# MCU.net
KiCad netlist of a schematic drawn in Altium Designer
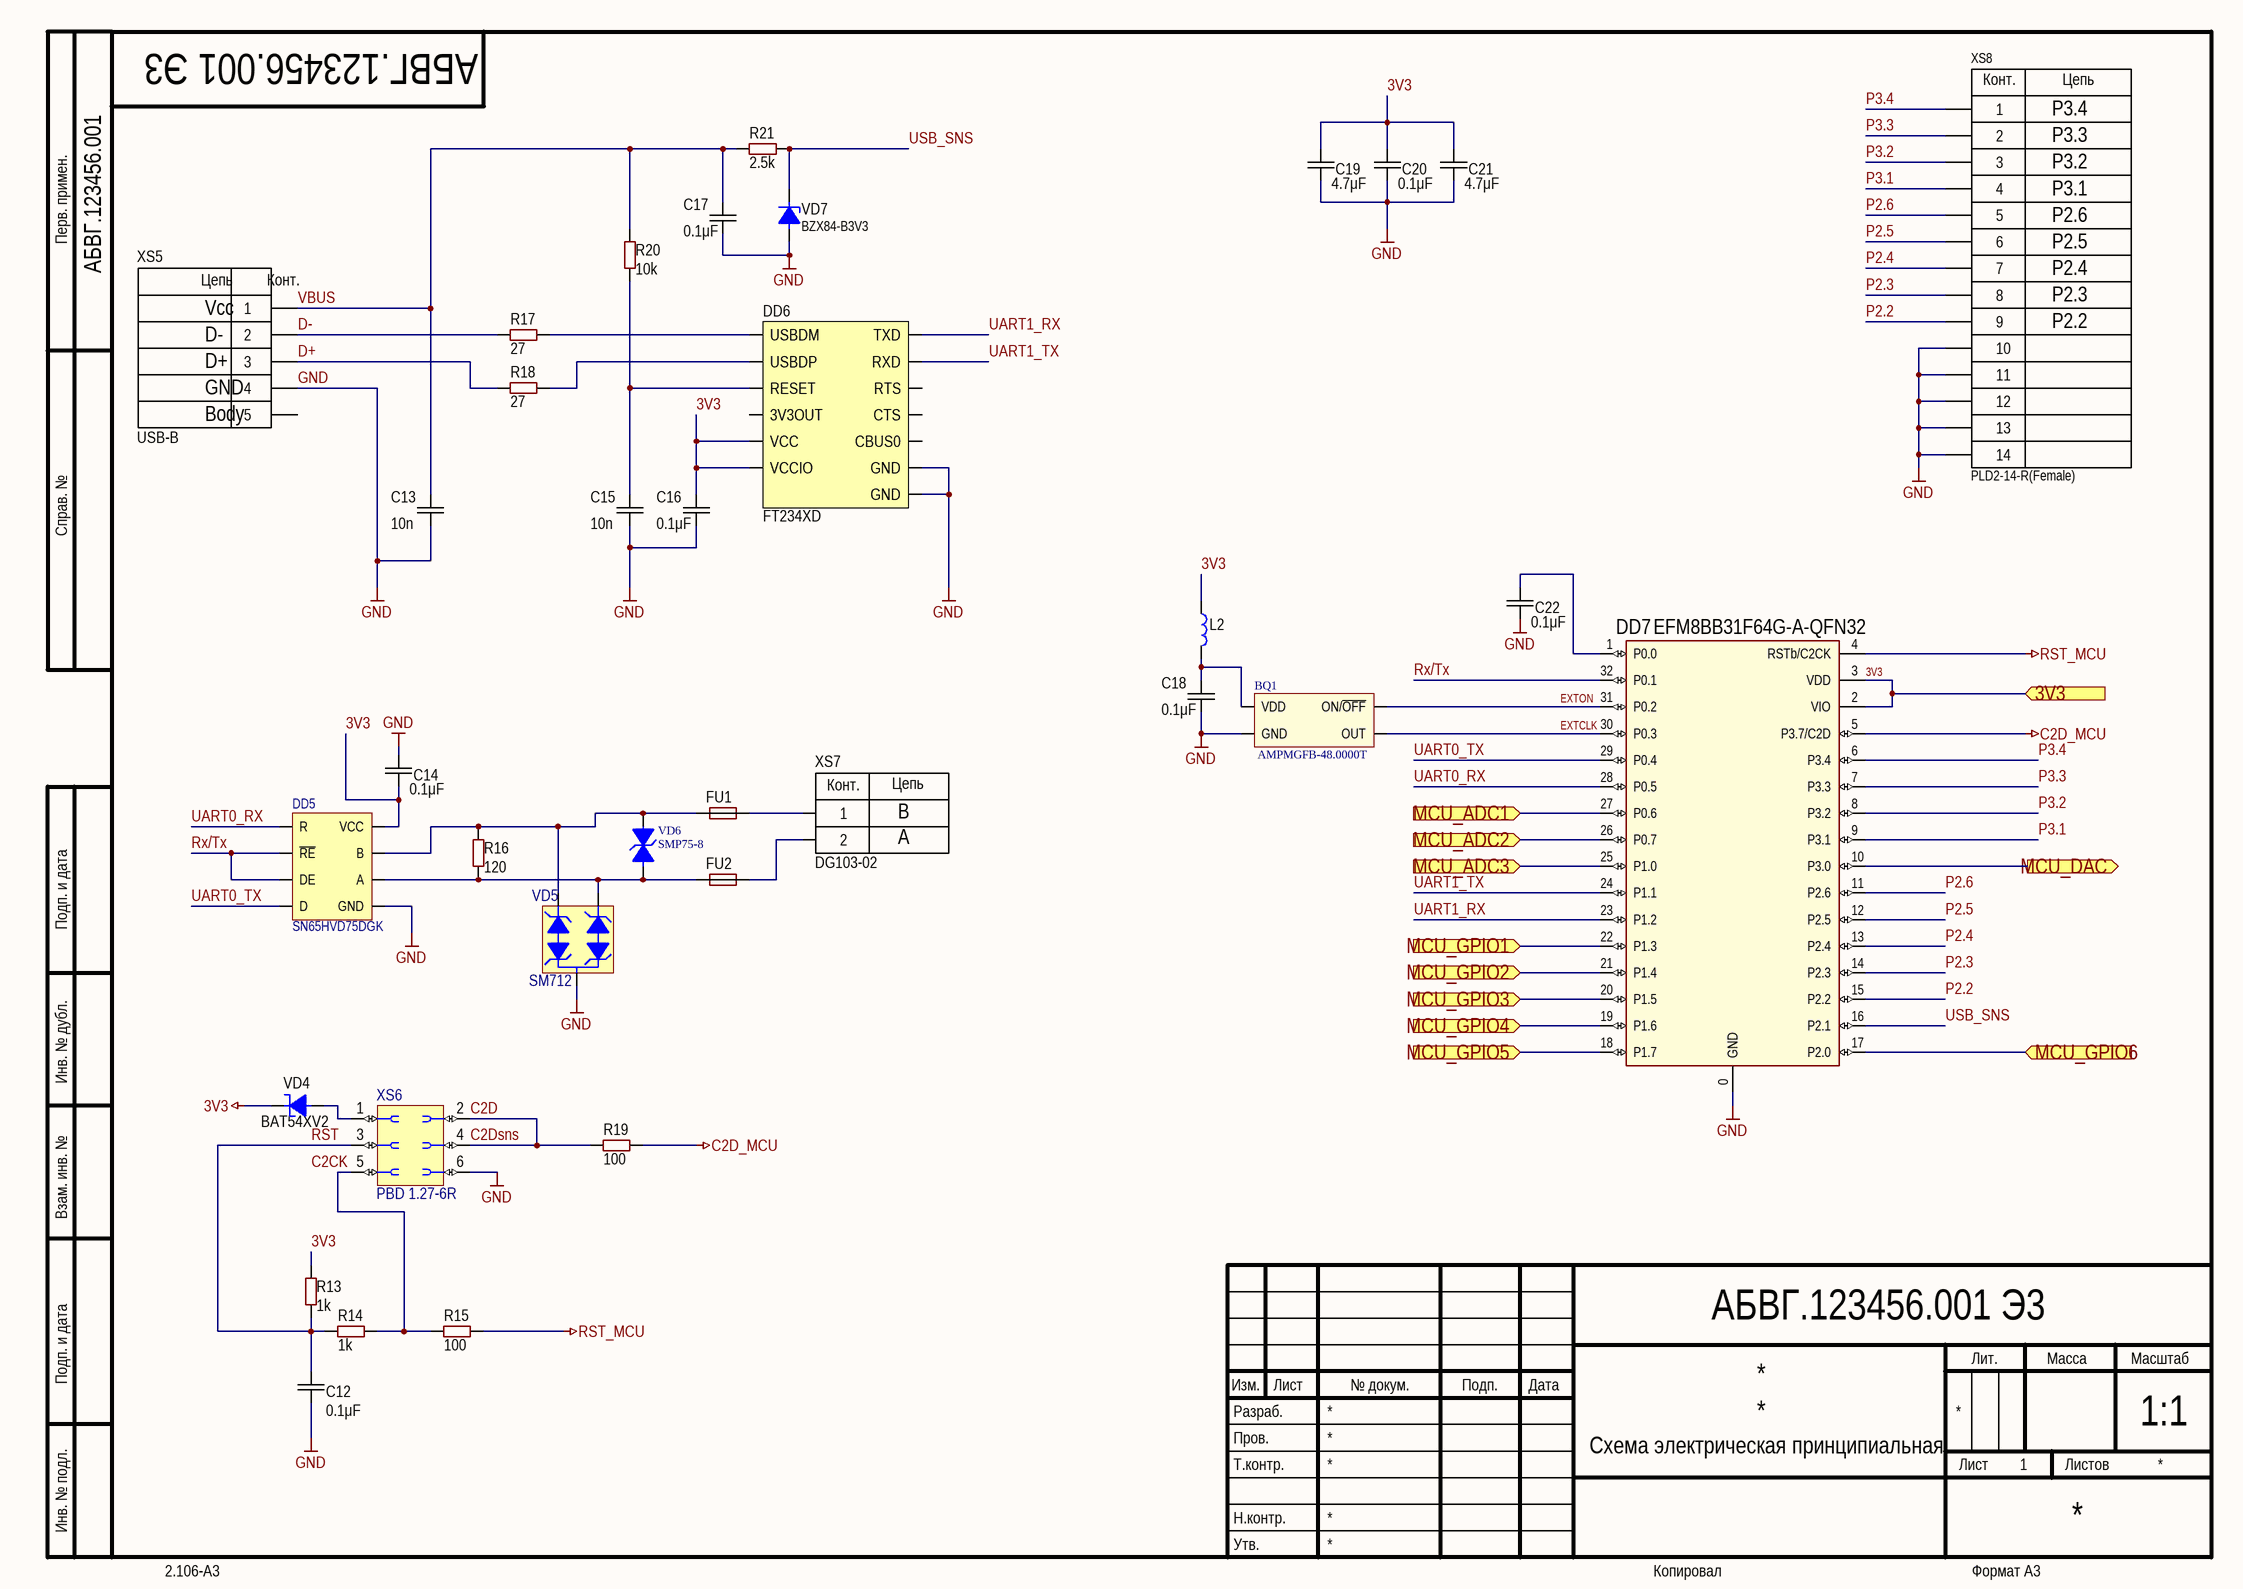
[diagram p0: MCU.SchDoc]

(export (version "E")
  (design (tool "Eeschema 10.0.6"))
  (components
    (comp (ref "BQ1")
      (value "AMPMGFB-48.0000T")
      (footprint "AMPMGFB(1.6x1.2)")
      (libsource (lib "oscilator") (part "AMPMGFB-48.0000T"))
    )
    (comp (ref "C12")
      (value "0.1μF")
      (footprint "CAP: 0603")
      (fields
        (field (name "MANUFACTURER") "Yageo")
        (field (name "PARTNUMBER") "CC0603KRX7R7BB104")
        (field (name "VALUEMANUFACTURERPARTNUMBER") "Ceramic capacitor, 0.1μF, X7R, ±10%, 16V, 0603, -55...+125°C")
      )
      (libsource (lib "capacitor") (part "Ceramic_0603"))
    )
    (comp (ref "C13")
      (value "10n")
      (footprint "CAP: 0603")
      (fields
        (field (name "MANUFACTURER") "Yageo")
        (field (name "PARTNUMBER") "CC0603KRX7R7BB104")
        (field (name "VALUEMANUFACTURERPARTNUMBER") "Ceramic capacitor, 10n, X7R, ±10%, 16V, 0603, -55...+125°C")
      )
      (libsource (lib "capacitor") (part "Ceramic_0603"))
    )
    (comp (ref "C14")
      (value "0.1μF")
      (footprint "CAP: 0603")
      (fields
        (field (name "MANUFACTURER") "Yageo")
        (field (name "PARTNUMBER") "CC0603KRX7R7BB104")
        (field (name "VALUEMANUFACTURERPARTNUMBER") "Ceramic capacitor, 0.1μF, X7R, ±10%, 16V, 0603, -55...+125°C")
      )
      (libsource (lib "capacitor") (part "Ceramic_0603"))
    )
    (comp (ref "C15")
      (value "10n")
      (footprint "CAP: 0603")
      (fields
        (field (name "MANUFACTURER") "Yageo")
        (field (name "PARTNUMBER") "CC0603KRX7R7BB104")
        (field (name "VALUEMANUFACTURERPARTNUMBER") "Ceramic capacitor, 10n, X7R, ±10%, 16V, 0603, -55...+125°C")
      )
      (libsource (lib "capacitor") (part "Ceramic_0603"))
    )
    (comp (ref "C16")
      (value "0.1μF")
      (footprint "CAP: 0603")
      (fields
        (field (name "MANUFACTURER") "Yageo")
        (field (name "PARTNUMBER") "CC0603KRX7R7BB104")
        (field (name "VALUEMANUFACTURERPARTNUMBER") "Ceramic capacitor, 0.1μF, X7R, ±10%, 16V, 0603, -55...+125°C")
      )
      (libsource (lib "capacitor") (part "Ceramic_0603"))
    )
    (comp (ref "C17")
      (value "0.1μF")
      (footprint "CAP: 0603")
      (fields
        (field (name "MANUFACTURER") "Yageo")
        (field (name "PARTNUMBER") "CC0603KRX7R7BB104")
        (field (name "VALUEMANUFACTURERPARTNUMBER") "Ceramic capacitor, 0.1μF, X7R, ±10%, 16V, 0603, -55...+125°C")
      )
      (libsource (lib "capacitor") (part "Ceramic_0603"))
    )
    (comp (ref "C18")
      (value "0.1μF")
      (footprint "CAP: 0603")
      (fields
        (field (name "MANUFACTURER") "Yageo")
        (field (name "PARTNUMBER") "CC0603KRX7R7BB104")
        (field (name "VALUEMANUFACTURERPARTNUMBER") "Ceramic capacitor, 0.1μF, X7R, ±10%, 16V, 0603, -55...+125°C")
      )
      (libsource (lib "capacitor") (part "Ceramic_0603"))
    )
    (comp (ref "C19")
      (value "4.7μF")
      (footprint "CAP: 0603")
      (fields
        (field (name "MANUFACTURER") "Yageo")
        (field (name "PARTNUMBER") "CC0603KRX7R7BB104")
        (field (name "VALUEMANUFACTURERPARTNUMBER") "Ceramic capacitor, 4.7μF, X7R, ±10%, 16V, 0603, -55...+125°C")
      )
      (libsource (lib "capacitor") (part "Ceramic_0603"))
    )
    (comp (ref "C20")
      (value "0.1μF")
      (footprint "CAP: 0603")
      (fields
        (field (name "MANUFACTURER") "Yageo")
        (field (name "PARTNUMBER") "CC0603KRX7R7BB104")
        (field (name "VALUEMANUFACTURERPARTNUMBER") "Ceramic capacitor, 0.1μF, X7R, ±10%, 16V, 0603, -55...+125°C")
      )
      (libsource (lib "capacitor") (part "Ceramic_0603"))
    )
    (comp (ref "C21")
      (value "4.7μF")
      (footprint "CAP: 0603")
      (fields
        (field (name "MANUFACTURER") "Yageo")
        (field (name "PARTNUMBER") "CC0603KRX7R7BB104")
        (field (name "VALUEMANUFACTURERPARTNUMBER") "Ceramic capacitor, 4.7μF, X7R, ±10%, 16V, 0603, -55...+125°C")
      )
      (libsource (lib "capacitor") (part "Ceramic_0603"))
    )
    (comp (ref "C22")
      (value "0.1μF")
      (footprint "CAP: 0603")
      (fields
        (field (name "MANUFACTURER") "Yageo")
        (field (name "PARTNUMBER") "CC0603KRX7R7BB104")
        (field (name "VALUEMANUFACTURERPARTNUMBER") "Ceramic capacitor, 0.1μF, X7R, ±10%, 16V, 0603, -55...+125°C")
      )
      (libsource (lib "capacitor") (part "Ceramic_0603"))
    )
    (comp (ref "DD5")
      (value "SN65HVD75DGK")
      (footprint "VSSOP-8")
      (description "RS-485/422")
      (libsource (lib "ic-interface") (part "SN65HVD72DGK"))
    )
    (comp (ref "DD6")
      (value "FT234XD")
      (footprint "12-DFN")
      (description "USB-UART")
      (libsource (lib "ic-interface") (part "FT234XD"))
    )
    (comp (ref "DD7")
      (value "EFM8BB31F64G-A-QFN32")
      (footprint "32-QFN(4x4)")
      (description "8051 MCU Core")
      (libsource (lib "ic-mcu") (part "EFM8BB31F64G-A-QFN32"))
    )
    (comp (ref "FU1")
      (value "~")
      (footprint "FUSE: 0603")
      (fields
        (field (name "MANUFACTURER") "Littelfuse")
        (field (name "VALUEMANUFACTURERPARTNUMBER") "Electromechanics relay, 250VAC, , 5x20mm, ")
        (field (name "PARTNUMBER") "01110501Z")
      )
      (libsource (lib "electromechanics") (part "Fuse"))
    )
    (comp (ref "FU2")
      (value "~")
      (footprint "FUSE: 0603")
      (fields
        (field (name "MANUFACTURER") "Littelfuse")
        (field (name "VALUEMANUFACTURERPARTNUMBER") "Electromechanics relay, 250VAC, , 5x20mm, ")
        (field (name "PARTNUMBER") "01110501Z")
      )
      (libsource (lib "electromechanics") (part "Fuse"))
    )
    (comp (ref "L2")
      (value "BLM18AG102SN1D")
      (footprint "IND: 0603")
      (description "100MHz 1K")
      (libsource (lib "inductor") (part "BLM18AG102SN1D"))
    )
    (comp (ref "R13")
      (value "1k")
      (footprint "RES: 0603")
      (fields
        (field (name "MANUFACTURER") "Yageo")
        (field (name "PARTNUMBER") "RC0603JR-07100RL")
        (field (name "VALUEMANUFACTURERPARTNUMBER") "Resistor film, 1k, ±5%, 0603, 0.1W, -55...+125°C")
      )
      (libsource (lib "resistor") (part "Resistor_0603"))
    )
    (comp (ref "R14")
      (value "1k")
      (footprint "RES: 0603")
      (fields
        (field (name "MANUFACTURER") "Yageo")
        (field (name "PARTNUMBER") "RC0603JR-07100RL")
        (field (name "VALUEMANUFACTURERPARTNUMBER") "Resistor film, 1k, ±5%, 0603, 0.1W, -55...+125°C")
      )
      (libsource (lib "") (part "Resistor_0603_1"))
    )
    (comp (ref "R15")
      (value "100")
      (footprint "RES: 0603")
      (fields
        (field (name "MANUFACTURER") "Yageo")
        (field (name "PARTNUMBER") "RC0603JR-07100RL")
        (field (name "VALUEMANUFACTURERPARTNUMBER") "Resistor film, 100, ±5%, 0603, 0.1W, -55...+125°C")
      )
      (libsource (lib "") (part "Resistor_0603_1"))
    )
    (comp (ref "R16")
      (value "120")
      (footprint "RES: 0603")
      (fields
        (field (name "MANUFACTURER") "Yageo")
        (field (name "PARTNUMBER") "RC0603JR-07100RL")
        (field (name "VALUEMANUFACTURERPARTNUMBER") "Resistor film, 120, ±5%, 0603, 0.1W, -55...+125°C")
      )
      (libsource (lib "") (part "Resistor_0603_1"))
    )
    (comp (ref "R17")
      (value "27")
      (footprint "RES: 0603")
      (fields
        (field (name "MANUFACTURER") "Yageo")
        (field (name "PARTNUMBER") "RC0603JR-07100RL")
        (field (name "VALUEMANUFACTURERPARTNUMBER") "Resistor film, 27, ±5%, 0603, 0.1W, -55...+125°C")
      )
      (libsource (lib "resistor") (part "Resistor_0603"))
    )
    (comp (ref "R18")
      (value "27")
      (footprint "RES: 0603")
      (fields
        (field (name "MANUFACTURER") "Yageo")
        (field (name "PARTNUMBER") "RC0603JR-07100RL")
        (field (name "VALUEMANUFACTURERPARTNUMBER") "Resistor film, 27, ±5%, 0603, 0.1W, -55...+125°C")
      )
      (libsource (lib "resistor") (part "Resistor_0603"))
    )
    (comp (ref "R19")
      (value "100")
      (footprint "RES: 0603")
      (fields
        (field (name "MANUFACTURER") "Yageo")
        (field (name "PARTNUMBER") "RC0603JR-07100RL")
        (field (name "VALUEMANUFACTURERPARTNUMBER") "Resistor film, 100, ±5%, 0603, 0.1W, -55...+125°C")
      )
      (libsource (lib "resistor") (part "Resistor_0603"))
    )
    (comp (ref "R20")
      (value "10k")
      (footprint "RES: 0603")
      (fields
        (field (name "MANUFACTURER") "Yageo")
        (field (name "PARTNUMBER") "RC0603JR-07100RL")
        (field (name "VALUEMANUFACTURERPARTNUMBER") "Resistor film, 10k, ±5%, 0603, 0.1W, -55...+125°C")
      )
      (libsource (lib "") (part "Resistor_0603_1"))
    )
    (comp (ref "R21")
      (value "2.5k")
      (footprint "RES: 0603")
      (fields
        (field (name "MANUFACTURER") "Yageo")
        (field (name "PARTNUMBER") "RC0603JR-07100RL")
        (field (name "VALUEMANUFACTURERPARTNUMBER") "Resistor film, 2.5k, ±5%, 0603, 0.1W, -55...+125°C")
      )
      (libsource (lib "resistor") (part "Resistor_0603"))
    )
    (comp (ref "VD4")
      (value "~")
      (footprint "DIODE: SOD523")
      (fields
        (field (name "MANUFACTURER") "Diodes Incorporated")
        (field (name "VALUEMANUFACTURERPARTNUMBER") "Schottky diode, 80V, 500mA, 1V, 15pF, SOD-123, -55...+150°C")
        (field (name "VOLTAGE") "80V")
        (field (name "PARTNUMBER") "BAT54XV2")
      )
      (libsource (lib "diode") (part "Schottky_single"))
    )
    (comp (ref "VD5")
      (value "SM712")
      (footprint "SOT23")
      (description "EIA RS-485 ±7V ±12V")
      (libsource (lib "diode") (part "SM712"))
    )
    (comp (ref "VD6")
      (value "SMP75-8")
      (footprint "DIODE: SMB")
      (libsource (lib "diode") (part "SMBJ10CA-TR"))
    )
    (comp (ref "VD7") (value "BZX84-B3V3") (footprint "SOT23") (libsource (lib "diode") (part "BZX84-B3V3")))
    (comp (ref "XS5")
      (value "USB-B")
      (footprint "CON: USB-B(Female vertical)")
      (libsource (lib "connector") (part "USB-B"))
    )
    (comp (ref "XS6")
      (value "PBD 1.27-6R")
      (footprint "CON: PLLD-6R(1.27)")
      (libsource (lib "connector") (part "PBD 1.27-6R"))
    )
    (comp (ref "XS7")
      (value "DG103-02")
      (footprint "DG103-02")
      (libsource (lib "connector") (part "DG103-02"))
    )
    (comp (ref "XS8")
      (value "PLD2-14-R(Female)")
      (footprint "CON: PLD2-14-R(Female)")
      (libsource (lib "connector") (part "PLD2-14(Female)"))
    )
  )
  (nets
    (net (code "2") (name "/C2D") (class "Default")
      (node (ref "R19") (pin "2") (pinfunction "2_2") (pintype "passive"))
      (node (ref "XS6") (pin "2") (pinfunction "2_2") (pintype "bidirectional"))
      (node (ref "XS6") (pin "4") (pinfunction "4_4") (pintype "bidirectional"))
    )
    (net (code "3") (name "/D+") (class "Default")
      (node (ref "R18") (pin "2") (pinfunction "2_2") (pintype "passive"))
      (node (ref "XS5") (pin "3") (pinfunction "3_3") (pintype "passive"))
    )
    (net (code "4") (name "/D-") (class "Default")
      (node (ref "R17") (pin "2") (pinfunction "2_2") (pintype "passive"))
      (node (ref "XS5") (pin "2") (pinfunction "2_2") (pintype "passive"))
    )
    (net (code "5") (name "/EXTCLK") (class "Default")
      (node (ref "BQ1") (pin "3") (pinfunction "OUT_3") (pintype "passive"))
      (node (ref "DD7") (pin "30") (pinfunction "P0.3_30") (pintype "bidirectional"))
    )
    (net (code "6") (name "/EXTON") (class "Default")
      (node (ref "BQ1") (pin "1") (pinfunction "ON/~{OFF}_1") (pintype "passive"))
      (node (ref "DD7") (pin "31") (pinfunction "P0.2_31") (pintype "bidirectional"))
    )
    (net (code "7") (name "/MCU_ADC1") (class "Default")
      (node (ref "DD7") (pin "27") (pinfunction "P0.6_27") (pintype "bidirectional"))
    )
    (net (code "8") (name "/MCU_ADC2") (class "Default")
      (node (ref "DD7") (pin "26") (pinfunction "P0.7_26") (pintype "bidirectional"))
    )
    (net (code "9") (name "/MCU_ADC3") (class "Default")
      (node (ref "DD7") (pin "25") (pinfunction "P1.0_25") (pintype "bidirectional"))
    )
    (net (code "10") (name "/MCU_DAC") (class "Default")
      (node (ref "DD7") (pin "10") (pinfunction "P3.0_10") (pintype "bidirectional"))
    )
    (net (code "11") (name "/MCU_GPIO1") (class "Default")
      (node (ref "DD7") (pin "22") (pinfunction "P1.3_22") (pintype "bidirectional"))
    )
    (net (code "12") (name "/MCU_GPIO2") (class "Default")
      (node (ref "DD7") (pin "21") (pinfunction "P1.4_21") (pintype "bidirectional"))
    )
    (net (code "13") (name "/MCU_GPIO3") (class "Default")
      (node (ref "DD7") (pin "20") (pinfunction "P1.5_20") (pintype "bidirectional"))
    )
    (net (code "14") (name "/MCU_GPIO4") (class "Default")
      (node (ref "DD7") (pin "19") (pinfunction "P1.6_19") (pintype "bidirectional"))
    )
    (net (code "15") (name "/MCU_GPIO5") (class "Default")
      (node (ref "DD7") (pin "18") (pinfunction "P1.7_18") (pintype "bidirectional"))
    )
    (net (code "16") (name "/MCU_GPIO6") (class "Default")
      (node (ref "DD7") (pin "17") (pinfunction "P2.0_17") (pintype "bidirectional"))
    )
    (net (code "17") (name "/P2.2") (class "Default")
      (node (ref "DD7") (pin "15") (pinfunction "P2.2_15") (pintype "bidirectional"))
      (node (ref "XS8") (pin "9") (pinfunction "9_9") (pintype "power_in"))
    )
    (net (code "18") (name "/P2.3") (class "Default")
      (node (ref "DD7") (pin "14") (pinfunction "P2.3_14") (pintype "bidirectional"))
      (node (ref "XS8") (pin "8") (pinfunction "8_8") (pintype "power_in"))
    )
    (net (code "19") (name "/P2.4") (class "Default")
      (node (ref "DD7") (pin "13") (pinfunction "P2.4_13") (pintype "bidirectional"))
      (node (ref "XS8") (pin "7") (pinfunction "7_7") (pintype "power_in"))
    )
    (net (code "20") (name "/P2.5") (class "Default")
      (node (ref "DD7") (pin "12") (pinfunction "P2.5_12") (pintype "bidirectional"))
      (node (ref "XS8") (pin "6") (pinfunction "6_6") (pintype "power_in"))
    )
    (net (code "21") (name "/P2.6") (class "Default")
      (node (ref "DD7") (pin "11") (pinfunction "P2.6_11") (pintype "bidirectional"))
      (node (ref "XS8") (pin "5") (pinfunction "5_5") (pintype "power_in"))
    )
    (net (code "22") (name "/P3.1") (class "Default")
      (node (ref "DD7") (pin "9") (pinfunction "P3.1_9") (pintype "bidirectional"))
      (node (ref "XS8") (pin "4") (pinfunction "4_4") (pintype "power_in"))
    )
    (net (code "23") (name "/P3.2") (class "Default")
      (node (ref "DD7") (pin "8") (pinfunction "P3.2_8") (pintype "bidirectional"))
      (node (ref "XS8") (pin "3") (pinfunction "3_3") (pintype "power_in"))
    )
    (net (code "24") (name "/P3.3") (class "Default")
      (node (ref "DD7") (pin "7") (pinfunction "P3.3_7") (pintype "bidirectional"))
      (node (ref "XS8") (pin "2") (pinfunction "2_2") (pintype "passive"))
    )
    (net (code "25") (name "/P3.4") (class "Default")
      (node (ref "DD7") (pin "6") (pinfunction "P3.4_6") (pintype "bidirectional"))
      (node (ref "XS8") (pin "1") (pinfunction "1_1") (pintype "passive"))
    )
    (net (code "26") (name "/RST") (class "Default")
      (node (ref "C12") (pin "2") (pinfunction "2_2") (pintype "passive"))
      (node (ref "R13") (pin "2") (pinfunction "2_2") (pintype "passive"))
      (node (ref "R14") (pin "1") (pinfunction "1_1") (pintype "passive"))
      (node (ref "XS6") (pin "3") (pinfunction "3_3") (pintype "bidirectional"))
    )
    (net (code "27") (name "/Rx{slash}Tx") (class "Default")
      (node (ref "DD5") (pin "2") (pinfunction "~{RE}_2") (pintype "passive"))
      (node (ref "DD5") (pin "3") (pinfunction "DE_3") (pintype "passive"))
      (node (ref "DD7") (pin "32") (pinfunction "P0.1_32") (pintype "bidirectional"))
    )
    (net (code "28") (name "/UART0_RX") (class "Default")
      (node (ref "DD5") (pin "1") (pinfunction "R_1") (pintype "passive"))
      (node (ref "DD7") (pin "28") (pinfunction "P0.5_28") (pintype "bidirectional"))
    )
    (net (code "29") (name "/UART0_TX") (class "Default")
      (node (ref "DD5") (pin "4") (pinfunction "D_4") (pintype "passive"))
      (node (ref "DD7") (pin "29") (pinfunction "P0.4_29") (pintype "bidirectional"))
    )
    (net (code "30") (name "/UART1_RX") (class "Default")
      (node (ref "DD6") (pin "7") (pinfunction "TXD_7") (pintype "passive"))
      (node (ref "DD7") (pin "23") (pinfunction "P1.2_23") (pintype "bidirectional"))
    )
    (net (code "31") (name "/UART1_TX") (class "Default")
      (node (ref "DD6") (pin "10") (pinfunction "RXD_10") (pintype "passive"))
      (node (ref "DD7") (pin "24") (pinfunction "P1.1_24") (pintype "bidirectional"))
    )
    (net (code "32") (name "/USB_SNS") (class "Default")
      (node (ref "DD7") (pin "16") (pinfunction "P2.1_16") (pintype "bidirectional"))
      (node (ref "R21") (pin "1") (pinfunction "1_1") (pintype "passive"))
      (node (ref "VD7") (pin "2") (pinfunction "1_2") (pintype "passive"))
    )
    (net (code "33") (name "/VBUS") (class "Default")
      (node (ref "C13") (pin "2") (pinfunction "2_2") (pintype "passive"))
      (node (ref "C17") (pin "2") (pinfunction "2_2") (pintype "passive"))
      (node (ref "R20") (pin "2") (pinfunction "2_2") (pintype "passive"))
      (node (ref "R21") (pin "2") (pinfunction "2_2") (pintype "passive"))
      (node (ref "XS5") (pin "1") (pinfunction "1_1") (pintype "passive"))
    )
    (net (code "34") (name "3V3") (class "Default")
      (node (ref "C14") (pin "1") (pinfunction "1_1") (pintype "passive"))
      (node (ref "C16") (pin "2") (pinfunction "2_2") (pintype "passive"))
      (node (ref "C19") (pin "2") (pinfunction "2_2") (pintype "passive"))
      (node (ref "C20") (pin "2") (pinfunction "2_2") (pintype "passive"))
      (node (ref "C21") (pin "2") (pinfunction "2_2") (pintype "passive"))
      (node (ref "DD5") (pin "8") (pinfunction "VCC_8") (pintype "passive"))
      (node (ref "DD6") (pin "4") (pinfunction "VCC_4") (pintype "passive"))
      (node (ref "DD6") (pin "9") (pinfunction "VCCIO_9") (pintype "passive"))
      (node (ref "DD7") (pin "2") (pinfunction "VIO_2") (pintype "passive"))
      (node (ref "DD7") (pin "3") (pinfunction "VDD_3") (pintype "passive"))
      (node (ref "L2") (pin "1") (pinfunction "1_1") (pintype "passive"))
      (node (ref "R13") (pin "1") (pinfunction "1_1") (pintype "passive"))
      (node (ref "VD4") (pin "2") (pinfunction "2_2") (pintype "passive"))
    )
    (net (code "35") (name "C2D_MCU") (class "Default")
      (node (ref "DD7") (pin "5") (pinfunction "P3.7/C2D_5") (pintype "bidirectional"))
      (node (ref "R19") (pin "1") (pinfunction "1_1") (pintype "passive"))
    )
    (net (code "36") (name "GND") (class "Default")
      (node (ref "BQ1") (pin "2") (pinfunction "GND_2") (pintype "passive"))
      (node (ref "C12") (pin "1") (pinfunction "1_1") (pintype "passive"))
      (node (ref "C13") (pin "1") (pinfunction "1_1") (pintype "passive"))
      (node (ref "C14") (pin "2") (pinfunction "2_2") (pintype "passive"))
      (node (ref "C15") (pin "1") (pinfunction "1_1") (pintype "passive"))
      (node (ref "C16") (pin "1") (pinfunction "1_1") (pintype "passive"))
      (node (ref "C17") (pin "1") (pinfunction "1_1") (pintype "passive"))
      (node (ref "C18") (pin "1") (pinfunction "1_1") (pintype "passive"))
      (node (ref "C19") (pin "1") (pinfunction "1_1") (pintype "passive"))
      (node (ref "C20") (pin "1") (pinfunction "1_1") (pintype "passive"))
      (node (ref "C21") (pin "1") (pinfunction "1_1") (pintype "passive"))
      (node (ref "C22") (pin "1") (pinfunction "1_1") (pintype "passive"))
      (node (ref "DD5") (pin "5") (pinfunction "GND_5") (pintype "passive"))
      (node (ref "DD6") (pin "13") (pinfunction "GND_13") (pintype "passive"))
      (node (ref "DD6") (pin "5") (pinfunction "GND_5") (pintype "passive"))
      (node (ref "DD7") (pin "0") (pinfunction "GND_0") (pintype "passive"))
      (node (ref "VD5") (pin "3") (pinfunction "3_3") (pintype "passive"))
      (node (ref "VD7") (pin "1") (pinfunction "2_1") (pintype "passive"))
      (node (ref "XS5") (pin "4") (pinfunction "4_4") (pintype "passive"))
      (node (ref "XS6") (pin "6") (pinfunction "6_6") (pintype "bidirectional"))
      (node (ref "XS8") (pin "10") (pinfunction "10_10") (pintype "power_in"))
      (node (ref "XS8") (pin "11") (pinfunction "11_11") (pintype "power_in"))
      (node (ref "XS8") (pin "12") (pinfunction "12_12") (pintype "power_in"))
      (node (ref "XS8") (pin "13") (pinfunction "13_13") (pintype "power_in"))
      (node (ref "XS8") (pin "14") (pinfunction "14_14") (pintype "power_in"))
    )
    (net (code "37") (name "Net-(BQ1-VDD)") (class "Default")
      (node (ref "BQ1") (pin "4") (pinfunction "VDD_4") (pintype "passive"))
      (node (ref "C18") (pin "2") (pinfunction "2_2") (pintype "passive"))
      (node (ref "L2") (pin "2") (pinfunction "2_2") (pintype "passive"))
    )
    (net (code "38") (name "Net-(DD5-A)") (class "Default")
      (node (ref "DD5") (pin "6") (pinfunction "A_6") (pintype "passive"))
      (node (ref "FU2") (pin "1") (pinfunction "1_1") (pintype "passive"))
      (node (ref "R16") (pin "1") (pinfunction "1_1") (pintype "passive"))
      (node (ref "VD5") (pin "2") (pinfunction "2_2") (pintype "passive"))
      (node (ref "VD6") (pin "1") (pinfunction "1_1") (pintype "passive"))
    )
    (net (code "39") (name "Net-(DD5-B)") (class "Default")
      (node (ref "DD5") (pin "7") (pinfunction "B_7") (pintype "passive"))
      (node (ref "FU1") (pin "1") (pinfunction "1_1") (pintype "passive"))
      (node (ref "R16") (pin "2") (pinfunction "2_2") (pintype "passive"))
      (node (ref "VD5") (pin "1") (pinfunction "1_1") (pintype "passive"))
      (node (ref "VD6") (pin "2") (pinfunction "2_2") (pintype "passive"))
    )
    (net (code "40") (name "Net-(DD6-RESET)") (class "Default")
      (node (ref "C15") (pin "2") (pinfunction "2_2") (pintype "passive"))
      (node (ref "DD6") (pin "2") (pinfunction "RESET_2") (pintype "passive"))
      (node (ref "R20") (pin "1") (pinfunction "1_1") (pintype "passive"))
    )
    (net (code "41") (name "Net-(DD6-USBDM)") (class "Default")
      (node (ref "DD6") (pin "1") (pinfunction "USBDM_1") (pintype "passive"))
      (node (ref "R17") (pin "1") (pinfunction "1_1") (pintype "passive"))
    )
    (net (code "42") (name "Net-(DD6-USBDP)") (class "Default")
      (node (ref "DD6") (pin "12") (pinfunction "USBDP_12") (pintype "passive"))
      (node (ref "R18") (pin "1") (pinfunction "1_1") (pintype "passive"))
    )
    (net (code "43") (name "Net-(DD7-P0.0)") (class "Default")
      (node (ref "C22") (pin "2") (pinfunction "2_2") (pintype "passive"))
      (node (ref "DD7") (pin "1") (pinfunction "P0.0_1") (pintype "bidirectional"))
    )
    (net (code "44") (name "Net-(FU1-Pad2)") (class "Default")
      (node (ref "FU1") (pin "2") (pinfunction "2_2") (pintype "passive"))
      (node (ref "XS7") (pin "1") (pinfunction "1_1") (pintype "passive"))
    )
    (net (code "45") (name "Net-(FU2-Pad2)") (class "Default")
      (node (ref "FU2") (pin "2") (pinfunction "2_2") (pintype "passive"))
      (node (ref "XS7") (pin "2") (pinfunction "2_2") (pintype "passive"))
    )
    (net (code "46") (name "Net-(R14-Pad2)") (class "Default")
      (node (ref "R14") (pin "2") (pinfunction "2_2") (pintype "passive"))
      (node (ref "R15") (pin "1") (pinfunction "1_1") (pintype "passive"))
      (node (ref "XS6") (pin "5") (pinfunction "5_5") (pintype "bidirectional"))
    )
    (net (code "47") (name "Net-(VD4-Pad1)") (class "Default")
      (node (ref "VD4") (pin "1") (pinfunction "1_1") (pintype "passive"))
      (node (ref "XS6") (pin "1") (pinfunction "1_1") (pintype "bidirectional"))
    )
    (net (code "48") (name "RST_MCU") (class "Default")
      (node (ref "DD7") (pin "4") (pinfunction "RSTb/C2CK_4") (pintype "passive"))
      (node (ref "R15") (pin "2") (pinfunction "2_2") (pintype "passive"))
    )
    (net (code "49") (name "unconnected-(DD6-3V3OUT-Pad3)") (class "Default")
      (node (ref "DD6") (pin "3") (pinfunction "3V3OUT_3") (pintype "passive"))
    )
    (net (code "50") (name "unconnected-(DD6-CBUS0-Pad6)") (class "Default")
      (node (ref "DD6") (pin "6") (pinfunction "CBUS0_6") (pintype "passive"))
    )
    (net (code "51") (name "unconnected-(DD6-CTS-Pad11)") (class "Default")
      (node (ref "DD6") (pin "11") (pinfunction "CTS_11") (pintype "passive"))
    )
    (net (code "52") (name "unconnected-(DD6-RTS-Pad8)") (class "Default")
      (node (ref "DD6") (pin "8") (pinfunction "RTS_8") (pintype "passive"))
    )
    (net (code "53") (name "unconnected-(XS5-Pad5)") (class "Default")
      (node (ref "XS5") (pin "5") (pinfunction "5_5") (pintype "passive"))
    )
  )
)
